# mainNarrow.net
KiCad netlist of a schematic drawn in EAGLE
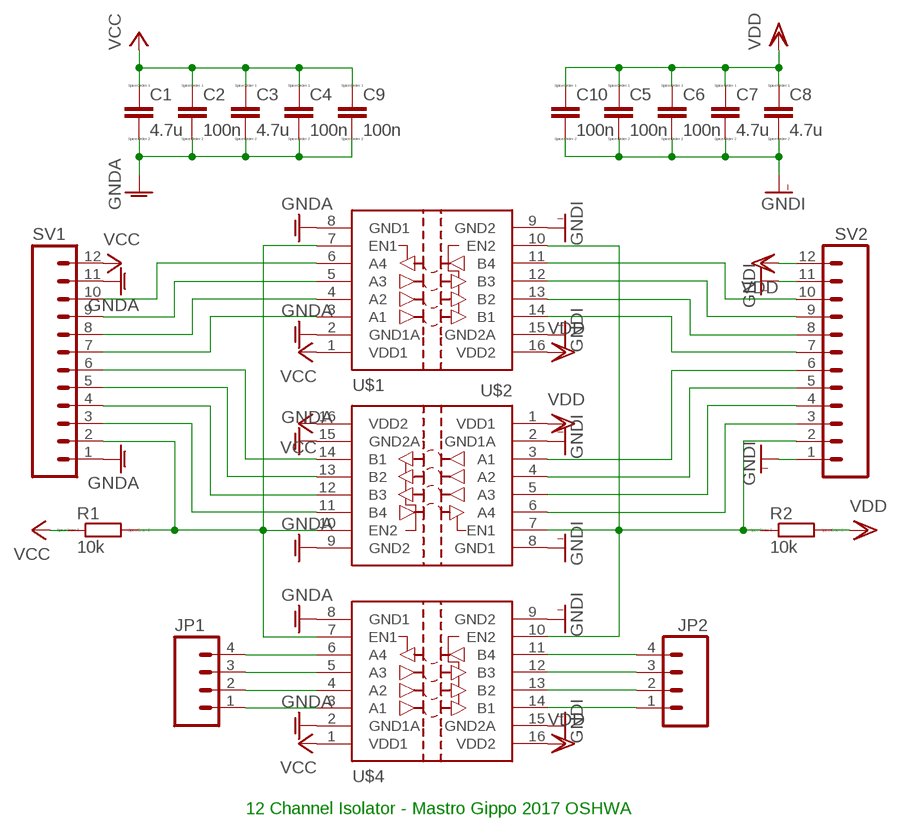
[diagram p0: schematic, sheet 1]

(export (version "E")
  (design (tool "Eeschema 10.0.6"))
  (components
    (comp (ref "C1")
      (value "4.7u")
      (footprint "eagle-import:C0805K")
      (libsource (lib "eagle-import") (part "C-EUC0805K"))
    )
    (comp (ref "C2")
      (value "100n")
      (footprint "eagle-import:C0805K")
      (libsource (lib "eagle-import") (part "C-EUC0805K"))
    )
    (comp (ref "C3")
      (value "4.7u")
      (footprint "eagle-import:C0805K")
      (libsource (lib "eagle-import") (part "C-EUC0805K"))
    )
    (comp (ref "C4")
      (value "100n")
      (footprint "eagle-import:C0805K")
      (libsource (lib "eagle-import") (part "C-EUC0805K"))
    )
    (comp (ref "C5")
      (value "100n")
      (footprint "eagle-import:C0805K")
      (libsource (lib "eagle-import") (part "C-EUC0805K"))
    )
    (comp (ref "C6")
      (value "100n")
      (footprint "eagle-import:C0805K")
      (libsource (lib "eagle-import") (part "C-EUC0805K"))
    )
    (comp (ref "C7")
      (value "4.7u")
      (footprint "eagle-import:C0805K")
      (libsource (lib "eagle-import") (part "C-EUC0805K"))
    )
    (comp (ref "C8")
      (value "4.7u")
      (footprint "eagle-import:C0805K")
      (libsource (lib "eagle-import") (part "C-EUC0805K"))
    )
    (comp (ref "C9")
      (value "100n")
      (footprint "eagle-import:C0805K")
      (libsource (lib "eagle-import") (part "C-EUC0805K"))
    )
    (comp (ref "C10")
      (value "100n")
      (footprint "eagle-import:C0805K")
      (libsource (lib "eagle-import") (part "C-EUC0805K"))
    )
    (comp (ref "JP1")
      (value "M04LONGPADS")
      (footprint "eagle-import:1X04_LONGPADS")
      (libsource (lib "eagle-import") (part "M04LONGPADS"))
    )
    (comp (ref "JP2")
      (value "M04LONGPADS")
      (footprint "eagle-import:1X04_LONGPADS")
      (libsource (lib "eagle-import") (part "M04LONGPADS"))
    )
    (comp (ref "R1")
      (value "10k")
      (footprint "eagle-import:M0805")
      (libsource (lib "eagle-import") (part "R-EU_M0805"))
    )
    (comp (ref "R2")
      (value "10k")
      (footprint "eagle-import:M0805")
      (libsource (lib "eagle-import") (part "R-EU_M0805"))
    )
    (comp (ref "SV1")
      (value "M12LONGPADS")
      (footprint "eagle-import:1X12_LONGPADS")
      (libsource (lib "eagle-import") (part "M12LONGPADS"))
    )
    (comp (ref "SV2")
      (value "M12LONGPADS")
      (footprint "eagle-import:1X12_LONGPADS")
      (libsource (lib "eagle-import") (part "M12LONGPADS"))
    )
    (comp (ref "U$1")
      (value "SI8441IS1")
      (footprint "eagle-import:SO16")
      (libsource (lib "eagle-import") (part "SI8441IS1"))
    )
    (comp (ref "U$2")
      (value "SI8441IS1")
      (footprint "eagle-import:SO16")
      (libsource (lib "eagle-import") (part "SI8441IS1"))
    )
    (comp (ref "U$4")
      (value "SI8441IS1")
      (footprint "eagle-import:SO16")
      (libsource (lib "eagle-import") (part "SI8441IS1"))
    )
  )
  (nets
    (net (code "1") (name "GNDA") (class "Default")
      (node (ref "C1") (pin "2") (pinfunction "2_2") (pintype "passive"))
      (node (ref "C2") (pin "2") (pinfunction "2_2") (pintype "passive"))
      (node (ref "C3") (pin "2") (pinfunction "2_2") (pintype "passive"))
      (node (ref "C4") (pin "2") (pinfunction "2_2") (pintype "passive"))
      (node (ref "C9") (pin "2") (pinfunction "2_2") (pintype "passive"))
      (node (ref "SV1") (pin "1") (pinfunction "1_1") (pintype "passive"))
      (node (ref "SV1") (pin "11") (pinfunction "11_11") (pintype "passive"))
      (node (ref "U$1") (pin "2") (pinfunction "GND1A_2") (pintype "power_in"))
      (node (ref "U$1") (pin "8") (pinfunction "GND1_8") (pintype "power_in"))
      (node (ref "U$2") (pin "15") (pinfunction "GND2A_15") (pintype "power_in"))
      (node (ref "U$2") (pin "9") (pinfunction "GND2_9") (pintype "power_in"))
      (node (ref "U$4") (pin "2") (pinfunction "GND1A_2") (pintype "power_in"))
      (node (ref "U$4") (pin "8") (pinfunction "GND1_8") (pintype "power_in"))
    )
    (net (code "2") (name "GNDI") (class "Default")
      (node (ref "C10") (pin "2") (pinfunction "2_2") (pintype "passive"))
      (node (ref "C5") (pin "2") (pinfunction "2_2") (pintype "passive"))
      (node (ref "C6") (pin "2") (pinfunction "2_2") (pintype "passive"))
      (node (ref "C7") (pin "2") (pinfunction "2_2") (pintype "passive"))
      (node (ref "C8") (pin "2") (pinfunction "2_2") (pintype "passive"))
      (node (ref "SV2") (pin "1") (pinfunction "1_1") (pintype "passive"))
      (node (ref "SV2") (pin "11") (pinfunction "11_11") (pintype "passive"))
      (node (ref "U$1") (pin "15") (pinfunction "GND2A_15") (pintype "power_in"))
      (node (ref "U$1") (pin "9") (pinfunction "GND2_9") (pintype "power_in"))
      (node (ref "U$2") (pin "2") (pinfunction "GND1A_2") (pintype "power_in"))
      (node (ref "U$2") (pin "8") (pinfunction "GND1_8") (pintype "power_in"))
      (node (ref "U$4") (pin "15") (pinfunction "GND2A_15") (pintype "power_in"))
      (node (ref "U$4") (pin "9") (pinfunction "GND2_9") (pintype "power_in"))
    )
    (net (code "3") (name "Net-(U$1-A1)") (class "Default")
      (node (ref "SV1") (pin "7") (pinfunction "7_7") (pintype "passive"))
      (node (ref "U$1") (pin "3") (pinfunction "A1_3") (pintype "input"))
    )
    (net (code "4") (name "Net-(U$1-A2)") (class "Default")
      (node (ref "SV1") (pin "8") (pinfunction "8_8") (pintype "passive"))
      (node (ref "U$1") (pin "4") (pinfunction "A2_4") (pintype "input"))
    )
    (net (code "5") (name "Net-(U$1-A3)") (class "Default")
      (node (ref "SV1") (pin "9") (pinfunction "9_9") (pintype "passive"))
      (node (ref "U$1") (pin "5") (pinfunction "A3_5") (pintype "input"))
    )
    (net (code "6") (name "Net-(U$1-A4)") (class "Default")
      (node (ref "SV1") (pin "10") (pinfunction "10_10") (pintype "passive"))
      (node (ref "U$1") (pin "6") (pinfunction "A4_6") (pintype "input"))
    )
    (net (code "7") (name "Net-(U$1-B1)") (class "Default")
      (node (ref "SV2") (pin "7") (pinfunction "7_7") (pintype "passive"))
      (node (ref "U$1") (pin "14") (pinfunction "B1_14") (pintype "output"))
    )
    (net (code "8") (name "Net-(U$1-B2)") (class "Default")
      (node (ref "SV2") (pin "8") (pinfunction "8_8") (pintype "passive"))
      (node (ref "U$1") (pin "13") (pinfunction "B2_13") (pintype "output"))
    )
    (net (code "9") (name "Net-(U$1-B3)") (class "Default")
      (node (ref "SV2") (pin "9") (pinfunction "9_9") (pintype "passive"))
      (node (ref "U$1") (pin "12") (pinfunction "B3_12") (pintype "output"))
    )
    (net (code "10") (name "Net-(U$1-B4)") (class "Default")
      (node (ref "SV2") (pin "10") (pinfunction "10_10") (pintype "passive"))
      (node (ref "U$1") (pin "11") (pinfunction "B4_11") (pintype "output"))
    )
    (net (code "11") (name "Net-(U$1-EN1)") (class "Default")
      (node (ref "R1") (pin "2") (pinfunction "2_2") (pintype "passive"))
      (node (ref "SV1") (pin "2") (pinfunction "2_2") (pintype "passive"))
      (node (ref "U$1") (pin "7") (pinfunction "EN1_7") (pintype "input"))
      (node (ref "U$2") (pin "10") (pinfunction "EN2_10") (pintype "input"))
      (node (ref "U$4") (pin "7") (pinfunction "EN1_7") (pintype "input"))
    )
    (net (code "12") (name "Net-(U$1-EN2)") (class "Default")
      (node (ref "R2") (pin "1") (pinfunction "1_1") (pintype "passive"))
      (node (ref "SV2") (pin "2") (pinfunction "2_2") (pintype "passive"))
      (node (ref "U$1") (pin "10") (pinfunction "EN2_10") (pintype "input"))
      (node (ref "U$2") (pin "7") (pinfunction "EN1_7") (pintype "input"))
      (node (ref "U$4") (pin "10") (pinfunction "EN2_10") (pintype "input"))
    )
    (net (code "13") (name "Net-(U$2-A1)") (class "Default")
      (node (ref "SV2") (pin "6") (pinfunction "6_6") (pintype "passive"))
      (node (ref "U$2") (pin "3") (pinfunction "A1_3") (pintype "input"))
    )
    (net (code "14") (name "Net-(U$2-A2)") (class "Default")
      (node (ref "SV2") (pin "5") (pinfunction "5_5") (pintype "passive"))
      (node (ref "U$2") (pin "4") (pinfunction "A2_4") (pintype "input"))
    )
    (net (code "15") (name "Net-(U$2-A3)") (class "Default")
      (node (ref "SV2") (pin "4") (pinfunction "4_4") (pintype "passive"))
      (node (ref "U$2") (pin "5") (pinfunction "A3_5") (pintype "input"))
    )
    (net (code "16") (name "Net-(U$2-A4)") (class "Default")
      (node (ref "SV2") (pin "3") (pinfunction "3_3") (pintype "passive"))
      (node (ref "U$2") (pin "6") (pinfunction "A4_6") (pintype "input"))
    )
    (net (code "17") (name "Net-(U$2-B1)") (class "Default")
      (node (ref "SV1") (pin "6") (pinfunction "6_6") (pintype "passive"))
      (node (ref "U$2") (pin "14") (pinfunction "B1_14") (pintype "output"))
    )
    (net (code "18") (name "Net-(U$2-B2)") (class "Default")
      (node (ref "SV1") (pin "5") (pinfunction "5_5") (pintype "passive"))
      (node (ref "U$2") (pin "13") (pinfunction "B2_13") (pintype "output"))
    )
    (net (code "19") (name "Net-(U$2-B3)") (class "Default")
      (node (ref "SV1") (pin "4") (pinfunction "4_4") (pintype "passive"))
      (node (ref "U$2") (pin "12") (pinfunction "B3_12") (pintype "output"))
    )
    (net (code "20") (name "Net-(U$2-B4)") (class "Default")
      (node (ref "SV1") (pin "3") (pinfunction "3_3") (pintype "passive"))
      (node (ref "U$2") (pin "11") (pinfunction "B4_11") (pintype "output"))
    )
    (net (code "21") (name "Net-(U$4-A1)") (class "Default")
      (node (ref "JP1") (pin "1") (pinfunction "1_1") (pintype "passive"))
      (node (ref "U$4") (pin "3") (pinfunction "A1_3") (pintype "input"))
    )
    (net (code "22") (name "Net-(U$4-A2)") (class "Default")
      (node (ref "JP1") (pin "2") (pinfunction "2_2") (pintype "passive"))
      (node (ref "U$4") (pin "4") (pinfunction "A2_4") (pintype "input"))
    )
    (net (code "23") (name "Net-(U$4-A3)") (class "Default")
      (node (ref "JP1") (pin "3") (pinfunction "3_3") (pintype "passive"))
      (node (ref "U$4") (pin "5") (pinfunction "A3_5") (pintype "input"))
    )
    (net (code "24") (name "Net-(U$4-A4)") (class "Default")
      (node (ref "JP1") (pin "4") (pinfunction "4_4") (pintype "passive"))
      (node (ref "U$4") (pin "6") (pinfunction "A4_6") (pintype "input"))
    )
    (net (code "25") (name "Net-(U$4-B1)") (class "Default")
      (node (ref "JP2") (pin "1") (pinfunction "1_1") (pintype "passive"))
      (node (ref "U$4") (pin "14") (pinfunction "B1_14") (pintype "output"))
    )
    (net (code "26") (name "Net-(U$4-B2)") (class "Default")
      (node (ref "JP2") (pin "2") (pinfunction "2_2") (pintype "passive"))
      (node (ref "U$4") (pin "13") (pinfunction "B2_13") (pintype "output"))
    )
    (net (code "27") (name "Net-(U$4-B3)") (class "Default")
      (node (ref "JP2") (pin "3") (pinfunction "3_3") (pintype "passive"))
      (node (ref "U$4") (pin "12") (pinfunction "B3_12") (pintype "output"))
    )
    (net (code "28") (name "Net-(U$4-B4)") (class "Default")
      (node (ref "JP2") (pin "4") (pinfunction "4_4") (pintype "passive"))
      (node (ref "U$4") (pin "11") (pinfunction "B4_11") (pintype "output"))
    )
    (net (code "29") (name "VCC") (class "Default")
      (node (ref "C1") (pin "1") (pinfunction "1_1") (pintype "passive"))
      (node (ref "C2") (pin "1") (pinfunction "1_1") (pintype "passive"))
      (node (ref "C3") (pin "1") (pinfunction "1_1") (pintype "passive"))
      (node (ref "C4") (pin "1") (pinfunction "1_1") (pintype "passive"))
      (node (ref "C9") (pin "1") (pinfunction "1_1") (pintype "passive"))
      (node (ref "R1") (pin "1") (pinfunction "1_1") (pintype "passive"))
      (node (ref "SV1") (pin "12") (pinfunction "12_12") (pintype "passive"))
      (node (ref "U$1") (pin "1") (pinfunction "VDD1_1") (pintype "power_in"))
      (node (ref "U$2") (pin "16") (pinfunction "VDD2_16") (pintype "power_in"))
      (node (ref "U$4") (pin "1") (pinfunction "VDD1_1") (pintype "power_in"))
    )
    (net (code "30") (name "VDD") (class "Default")
      (node (ref "C10") (pin "1") (pinfunction "1_1") (pintype "passive"))
      (node (ref "C5") (pin "1") (pinfunction "1_1") (pintype "passive"))
      (node (ref "C6") (pin "1") (pinfunction "1_1") (pintype "passive"))
      (node (ref "C7") (pin "1") (pinfunction "1_1") (pintype "passive"))
      (node (ref "C8") (pin "1") (pinfunction "1_1") (pintype "passive"))
      (node (ref "R2") (pin "2") (pinfunction "2_2") (pintype "passive"))
      (node (ref "SV2") (pin "12") (pinfunction "12_12") (pintype "passive"))
      (node (ref "U$1") (pin "16") (pinfunction "VDD2_16") (pintype "power_in"))
      (node (ref "U$2") (pin "1") (pinfunction "VDD1_1") (pintype "power_in"))
      (node (ref "U$4") (pin "16") (pinfunction "VDD2_16") (pintype "power_in"))
    )
  )
)
